# Connectors.net
KiCad netlist of a schematic drawn in Altium Designer
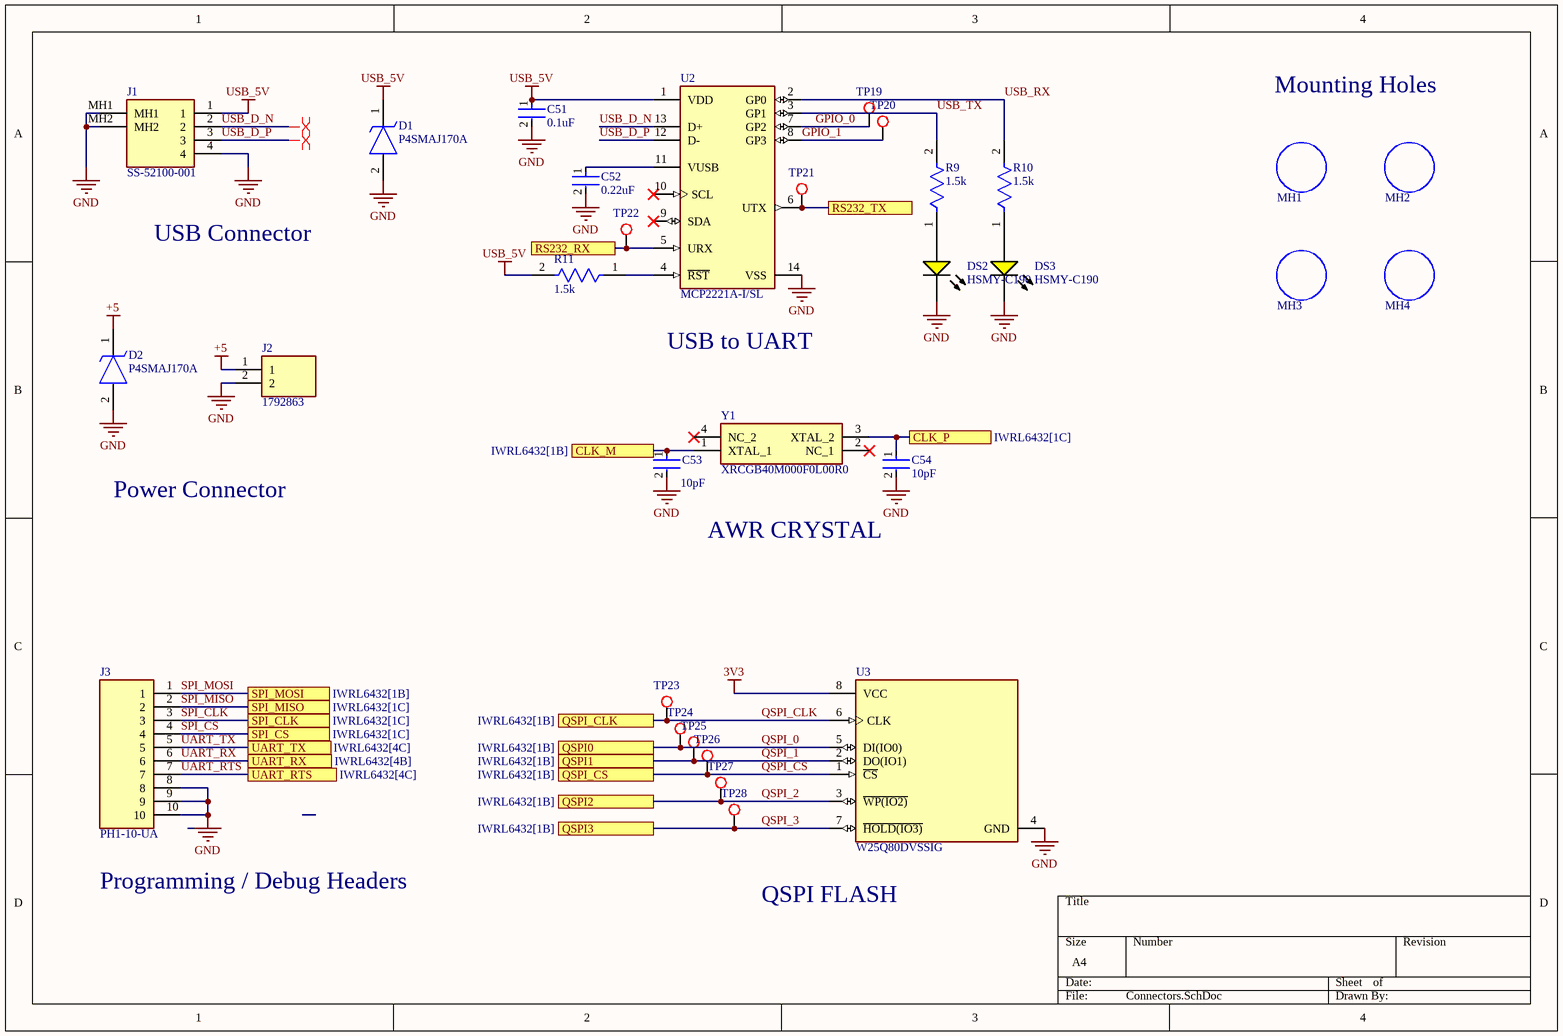
[diagram p0: Connectors.SchDoc]

(export (version "E")
  (design (tool "Eeschema 10.0.6"))
  (components
    (comp (ref "C51")
      (value "0.1uF")
      (footprint "FP-CC0603-DA-MFG")
      (description "CAP CER 0.1UF 10V X7R 0603")
      (fields
        (field (name "OCTOPART") "https://octopart.com/cc0603krx7r6bb104-yageo-9291607")
        (field (name "TOLERANCE") "0.1")
      )
      (libsource (lib "Altium Content Vault") (part "11868f565c42a9108669ba33697ecf6"))
    )
    (comp (ref "C52")
      (value "0.22uF")
      (footprint "FP-C0603C-CF-MFG")
      (description "C0603 0.22 μF X7R 30ppm/°C 10.00% 10 V")
      (fields (field (name "TOLERANCE") "0.1") (field (name "MANUFACTURER PART NUMBER") "C0603C224K8RAC"))
      (libsource (lib "Altium Content Vault") (part "b4654b650e69147ec39a6b967a45e02"))
    )
    (comp (ref "C53")
      (value "10pF")
      (footprint "FP-CL10-IPC_B")
      (description "Cap Ceramic 10pF 50V C0G ±0.25pF Pad SMD 0603 +125°C T/R")
      (fields (field (name "VOLTAGE") "50V"))
      (libsource (lib "Altium Content Vault") (part "b4654b650e69147ec39a6b967a45e02"))
    )
    (comp (ref "C54")
      (value "10pF")
      (footprint "FP-CL10-IPC_B")
      (description "Cap Ceramic 10pF 50V C0G ±0.25pF Pad SMD 0603 +125°C T/R")
      (fields (field (name "VOLTAGE") "50V"))
      (libsource (lib "Altium Content Vault") (part "b4654b650e69147ec39a6b967a45e02"))
    )
    (comp (ref "D1")
      (value "P4SMAJ170A")
      (footprint "SamacSys:DIOM5027X240N")
      (description "TVS Diode (Uni-directional)")
      (libsource (lib "*") (part "P4SMAJ170A"))
    )
    (comp (ref "D2")
      (value "P4SMAJ170A")
      (footprint "SamacSys:DIOM5027X240N")
      (description "TVS Diode (Uni-directional)")
      (libsource (lib "*") (part "P4SMAJ170A"))
    )
    (comp (ref "DS2")
      (value "HSMY-C190")
      (footprint "AVAG-HSMX-C190_V")
      (description "LED Uni-Color Yellow, 65 mW, 20 mA, -40 to 85 degC, 2-Pin SMD, RoHS, Tape and Reel")
      (fields (field (name "TOLERANCE") "1%"))
      (libsource (lib "Altium Content Vault") (part "LED-YELLOW-AK-2"))
    )
    (comp (ref "DS3")
      (value "HSMY-C190")
      (footprint "AVAG-HSMX-C190_V")
      (description "LED Uni-Color Yellow, 65 mW, 20 mA, -40 to 85 degC, 2-Pin SMD, RoHS, Tape and Reel")
      (fields (field (name "TOLERANCE") "1%"))
      (libsource (lib "Altium Content Vault") (part "LED-YELLOW-AK-2"))
    )
    (comp (ref "J1")
      (value "SS-52100-001")
      (footprint "SamacSys:SS52100001")
      (description "Connector")
      (fields (field (name "MOUSER PART NUMBER") "530-SS-52100-001"))
      (libsource (lib "*") (part "SS-52100-001"))
    )
    (comp (ref "J2")
      (value "1792863")
      (footprint "SamacSys:1792863")
      (description "Connector")
      (fields (field (name "MOUSER PART NUMBER") "651-1792863"))
      (libsource (lib "*") (part "1792863"))
    )
    (comp (ref "J3")
      (value "PH1-10-UA")
      (footprint "SamacSys:HDRV10W64P0X254_1X10_2540X249X886P")
      (description "Connector")
      (fields (field (name "MOUSER PART NUMBER") "737-PH1-10-UA"))
      (libsource (lib "*") (part "PH1-10-UA"))
    )
    (comp (ref "MH1")
      (value "MH?")
      (footprint "Mounting Hole")
      (libsource (lib "Schlib1") (part "Mounting Hole"))
    )
    (comp (ref "MH2")
      (value "MH?")
      (footprint "Mounting Hole")
      (libsource (lib "Schlib1") (part "Mounting Hole"))
    )
    (comp (ref "MH3")
      (value "MH?")
      (footprint "Mounting Hole")
      (libsource (lib "Schlib1") (part "Mounting Hole"))
    )
    (comp (ref "MH4")
      (value "MH?")
      (footprint "Mounting Hole")
      (libsource (lib "Schlib1") (part "Mounting Hole"))
    )
    (comp (ref "R9")
      (value "1.5k")
      (footprint "FP-RC1608-IPC_B")
      (description "Res Thick Film 0603 1.5kΩ 1% 0.1W ±100ppm/°C Molded SMD T/R")
      (fields (field (name "TOLERANCE") "1%"))
      (libsource (lib "Altium Content Vault") (part "1029c3af85768c4190bb7ad29bc67b5"))
    )
    (comp (ref "R10")
      (value "1.5k")
      (footprint "FP-RC1608-IPC_B")
      (description "Res Thick Film 0603 1.5kΩ 1% 0.1W ±100ppm/°C Molded SMD T/R")
      (fields (field (name "TOLERANCE") "1%"))
      (libsource (lib "Altium Content Vault") (part "1029c3af85768c4190bb7ad29bc67b5"))
    )
    (comp (ref "R11")
      (value "1.5k")
      (footprint "FP-RC1608-IPC_B")
      (description "Res Thick Film 0603 1.5kΩ 1% 0.1W ±100ppm/°C Molded SMD T/R")
      (fields (field (name "TOLERANCE") "1%"))
      (libsource (lib "Altium Content Vault") (part "1029c3af85768c4190bb7ad29bc67b5"))
    )
    (comp (ref "TP19") (value "TP_1") (footprint "Testpoint") (libsource (lib "Schlib1") (part "Testpoint")))
    (comp (ref "TP20") (value "TP_1") (footprint "Testpoint") (libsource (lib "Schlib1") (part "Testpoint")))
    (comp (ref "TP21") (value "TP_1") (footprint "Testpoint") (libsource (lib "Schlib1") (part "Testpoint")))
    (comp (ref "TP22") (value "TP_1") (footprint "Testpoint") (libsource (lib "Schlib1") (part "Testpoint")))
    (comp (ref "TP23") (value "TP_1") (footprint "Testpoint") (libsource (lib "Schlib1") (part "Testpoint")))
    (comp (ref "TP24") (value "TP_1") (footprint "Testpoint") (libsource (lib "Schlib1") (part "Testpoint")))
    (comp (ref "TP25") (value "TP_1") (footprint "Testpoint") (libsource (lib "Schlib1") (part "Testpoint")))
    (comp (ref "TP26") (value "TP_1") (footprint "Testpoint") (libsource (lib "Schlib1") (part "Testpoint")))
    (comp (ref "TP27") (value "TP_1") (footprint "Testpoint") (libsource (lib "Schlib1") (part "Testpoint")))
    (comp (ref "TP28") (value "TP_1") (footprint "Testpoint") (libsource (lib "Schlib1") (part "Testpoint")))
    (comp (ref "U2")
      (value "MCP2221A-I/SL")
      (footprint "FP-C04-065-SL-MFG")
      (description "IC USB TO I2C/UART 14SOIC")
      (fields
        (field (name "OCTOPART") "https://octopart.com/mcp2221a-i%2Fsl-microchip-71704986")
        (field (name "MANUFACTURER") "Microchip")
      )
      (libsource (lib "Altium Content Vault") (part "1b53208594fde27bd45fc2fa1d78706"))
    )
    (comp (ref "U3")
      (value "W25Q80DVSSIG")
      (footprint "FP-SS-MFG")
      (description "IC FLASH 8MBIT SPI 104MHZ 8SOIC")
      (libsource (lib "Altium Content Vault") (part "04025d3425be9a6c88c6bb112b73860"))
    )
    (comp (ref "Y1")
      (value "XRCGB40M000F0L00R0")
      (footprint "SamacSys:XRCGB")
      (description "Crystal or Oscillator")
      (fields (field (name "MOUSER PART NUMBER") "81-XRCGB40M000F0L0R0"))
      (libsource (lib "*") (part "XRCGB40M000F0L00R0"))
    )
  )
  (nets
    (net (code "1") (name "+5") (class "Default")
      (node (ref "D2") (pin "1") (pinfunction "K_1") (pintype "passive"))
      (node (ref "J2") (pin "1") (pinfunction "1_1") (pintype "passive"))
    )
    (net (code "2") (name "/CLK_M") (class "Default")
      (node (ref "C53") (pin "1") (pinfunction "1_1") (pintype "passive"))
      (node (ref "Y1") (pin "1") (pinfunction "XTAL_1_1") (pintype "passive"))
    )
    (net (code "3") (name "/CLK_P") (class "Default")
      (node (ref "C54") (pin "1") (pinfunction "1_1") (pintype "passive"))
      (node (ref "Y1") (pin "3") (pinfunction "XTAL_2_3") (pintype "passive"))
    )
    (net (code "4") (name "/GPIO_0") (class "Default")
      (node (ref "TP19") (pin "0") (pinfunction "0_0") (pintype "passive"))
      (node (ref "U2") (pin "7") (pinfunction "GP2_7") (pintype "bidirectional"))
    )
    (net (code "5") (name "/GPIO_1") (class "Default")
      (node (ref "TP20") (pin "0") (pinfunction "0_0") (pintype "passive"))
      (node (ref "U2") (pin "8") (pinfunction "GP3_8") (pintype "bidirectional"))
    )
    (net (code "6") (name "/QSPI_0") (class "Default")
      (node (ref "TP24") (pin "0") (pinfunction "0_0") (pintype "passive"))
      (node (ref "U3") (pin "5") (pinfunction "DI(IO0)_5") (pintype "bidirectional"))
    )
    (net (code "7") (name "/QSPI_1") (class "Default")
      (node (ref "TP25") (pin "0") (pinfunction "0_0") (pintype "passive"))
      (node (ref "U3") (pin "2") (pinfunction "DO(IO1)_2") (pintype "bidirectional"))
    )
    (net (code "8") (name "/QSPI_2") (class "Default")
      (node (ref "TP27") (pin "0") (pinfunction "0_0") (pintype "passive"))
      (node (ref "U3") (pin "3") (pinfunction "~{WP(IO2)}_3") (pintype "bidirectional"))
    )
    (net (code "9") (name "/QSPI_3") (class "Default")
      (node (ref "TP28") (pin "0") (pinfunction "0_0") (pintype "passive"))
      (node (ref "U3") (pin "7") (pinfunction "~{HOLD(IO3)}_7") (pintype "bidirectional"))
    )
    (net (code "10") (name "/QSPI_CLK") (class "Default")
      (node (ref "TP23") (pin "0") (pinfunction "0_0") (pintype "passive"))
      (node (ref "U3") (pin "6") (pinfunction "CLK_6") (pintype "input"))
    )
    (net (code "11") (name "/QSPI_CS") (class "Default")
      (node (ref "TP26") (pin "0") (pinfunction "0_0") (pintype "passive"))
      (node (ref "U3") (pin "1") (pinfunction "~{CS}_1") (pintype "input"))
    )
    (net (code "12") (name "/RS232_RX") (class "Default")
      (node (ref "TP22") (pin "0") (pinfunction "0_0") (pintype "passive"))
      (node (ref "U2") (pin "5") (pinfunction "URX_5") (pintype "input"))
    )
    (net (code "13") (name "/RS232_TX") (class "Default")
      (node (ref "TP21") (pin "0") (pinfunction "0_0") (pintype "passive"))
      (node (ref "U2") (pin "6") (pinfunction "UTX_6") (pintype "output"))
    )
    (net (code "14") (name "/SPI_CLK") (class "Default")
      (node (ref "J3") (pin "3") (pinfunction "3_3") (pintype "passive"))
    )
    (net (code "15") (name "/SPI_CS") (class "Default")
      (node (ref "J3") (pin "4") (pinfunction "4_4") (pintype "passive"))
    )
    (net (code "16") (name "/SPI_MISO") (class "Default")
      (node (ref "J3") (pin "2") (pinfunction "2_2") (pintype "passive"))
    )
    (net (code "17") (name "/SPI_MOSI") (class "Default")
      (node (ref "J3") (pin "1") (pinfunction "1_1") (pintype "passive"))
    )
    (net (code "18") (name "/UART_RTS") (class "Default")
      (node (ref "J3") (pin "7") (pinfunction "7_7") (pintype "passive"))
    )
    (net (code "19") (name "/UART_RX") (class "Default")
      (node (ref "J3") (pin "6") (pinfunction "6_6") (pintype "passive"))
    )
    (net (code "20") (name "/UART_TX") (class "Default")
      (node (ref "J3") (pin "5") (pinfunction "5_5") (pintype "passive"))
    )
    (net (code "21") (name "/USB_D_N") (class "Default")
      (node (ref "J1") (pin "2") (pinfunction "2_2") (pintype "passive"))
      (node (ref "U2") (pin "13") (pinfunction "D+_13") (pintype "power_in"))
    )
    (net (code "22") (name "/USB_D_P") (class "Default")
      (node (ref "J1") (pin "3") (pinfunction "3_3") (pintype "passive"))
      (node (ref "U2") (pin "12") (pinfunction "D-_12") (pintype "power_in"))
    )
    (net (code "23") (name "/USB_RX") (class "Default")
      (node (ref "R10") (pin "2") (pinfunction "2_2") (pintype "passive"))
      (node (ref "U2") (pin "2") (pinfunction "GP0_2") (pintype "bidirectional"))
    )
    (net (code "24") (name "/USB_TX") (class "Default")
      (node (ref "R9") (pin "2") (pinfunction "2_2") (pintype "passive"))
      (node (ref "U2") (pin "3") (pinfunction "GP1_3") (pintype "bidirectional"))
    )
    (net (code "25") (name "3V3") (class "Default")
      (node (ref "U3") (pin "8") (pinfunction "VCC_8") (pintype "power_in"))
    )
    (net (code "26") (name "GND") (class "Default")
      (node (ref "C51") (pin "2") (pinfunction "2_2") (pintype "passive"))
      (node (ref "C52") (pin "2") (pinfunction "2_2") (pintype "passive"))
      (node (ref "C53") (pin "2") (pinfunction "2_2") (pintype "passive"))
      (node (ref "C54") (pin "2") (pinfunction "2_2") (pintype "passive"))
      (node (ref "D1") (pin "2") (pinfunction "A_2") (pintype "passive"))
      (node (ref "D2") (pin "2") (pinfunction "A_2") (pintype "passive"))
      (node (ref "DS2") (pin "2") (pinfunction "K_2") (pintype "passive"))
      (node (ref "DS3") (pin "2") (pinfunction "K_2") (pintype "passive"))
      (node (ref "J1") (pin "4") (pinfunction "4_4") (pintype "passive"))
      (node (ref "J1") (pin "MH1") (pinfunction "MH1_MH1") (pintype "passive"))
      (node (ref "J1") (pin "MH2") (pinfunction "MH2_MH2") (pintype "passive"))
      (node (ref "J2") (pin "2") (pinfunction "2_2") (pintype "passive"))
      (node (ref "J3") (pin "10") (pinfunction "10_10") (pintype "passive"))
      (node (ref "J3") (pin "8") (pinfunction "8_8") (pintype "passive"))
      (node (ref "J3") (pin "9") (pinfunction "9_9") (pintype "passive"))
      (node (ref "U2") (pin "14") (pinfunction "VSS_14") (pintype "power_in"))
      (node (ref "U3") (pin "4") (pinfunction "GND_4") (pintype "power_in"))
    )
    (net (code "27") (name "Net-(DS2-A)") (class "Default")
      (node (ref "DS2") (pin "1") (pinfunction "A_1") (pintype "passive"))
      (node (ref "R9") (pin "1") (pinfunction "1_1") (pintype "passive"))
    )
    (net (code "28") (name "Net-(DS3-A)") (class "Default")
      (node (ref "DS3") (pin "1") (pinfunction "A_1") (pintype "passive"))
      (node (ref "R10") (pin "1") (pinfunction "1_1") (pintype "passive"))
    )
    (net (code "29") (name "Net-(U2-VUSB)") (class "Default")
      (node (ref "C52") (pin "1") (pinfunction "1_1") (pintype "passive"))
      (node (ref "U2") (pin "11") (pinfunction "VUSB_11") (pintype "power_in"))
    )
    (net (code "30") (name "Net-(U2-~{RST})") (class "Default")
      (node (ref "R11") (pin "1") (pinfunction "1_1") (pintype "passive"))
      (node (ref "U2") (pin "4") (pinfunction "~{RST}_4") (pintype "input"))
    )
    (net (code "31") (name "USB_5V") (class "Default")
      (node (ref "C51") (pin "1") (pinfunction "1_1") (pintype "passive"))
      (node (ref "D1") (pin "1") (pinfunction "K_1") (pintype "passive"))
      (node (ref "J1") (pin "1") (pinfunction "1_1") (pintype "passive"))
      (node (ref "R11") (pin "2") (pinfunction "2_2") (pintype "passive"))
      (node (ref "U2") (pin "1") (pinfunction "VDD_1") (pintype "power_in"))
    )
    (net (code "32") (name "unconnected-(U2-SCL-Pad10)") (class "Default")
      (node (ref "U2") (pin "10") (pinfunction "SCL_10") (pintype "input+no_connect"))
    )
    (net (code "33") (name "unconnected-(U2-SDA-Pad9)") (class "Default")
      (node (ref "U2") (pin "9") (pinfunction "SDA_9") (pintype "bidirectional+no_connect"))
    )
    (net (code "34") (name "unconnected-(Y1-NC_1-Pad2)") (class "Default")
      (node (ref "Y1") (pin "2") (pinfunction "NC_1_2") (pintype "passive+no_connect"))
    )
    (net (code "35") (name "unconnected-(Y1-NC_2-Pad4)") (class "Default")
      (node (ref "Y1") (pin "4") (pinfunction "NC_2_4") (pintype "passive+no_connect"))
    )
  )
)
